# touch.net
KiCad netlist of a schematic drawn in EAGLE
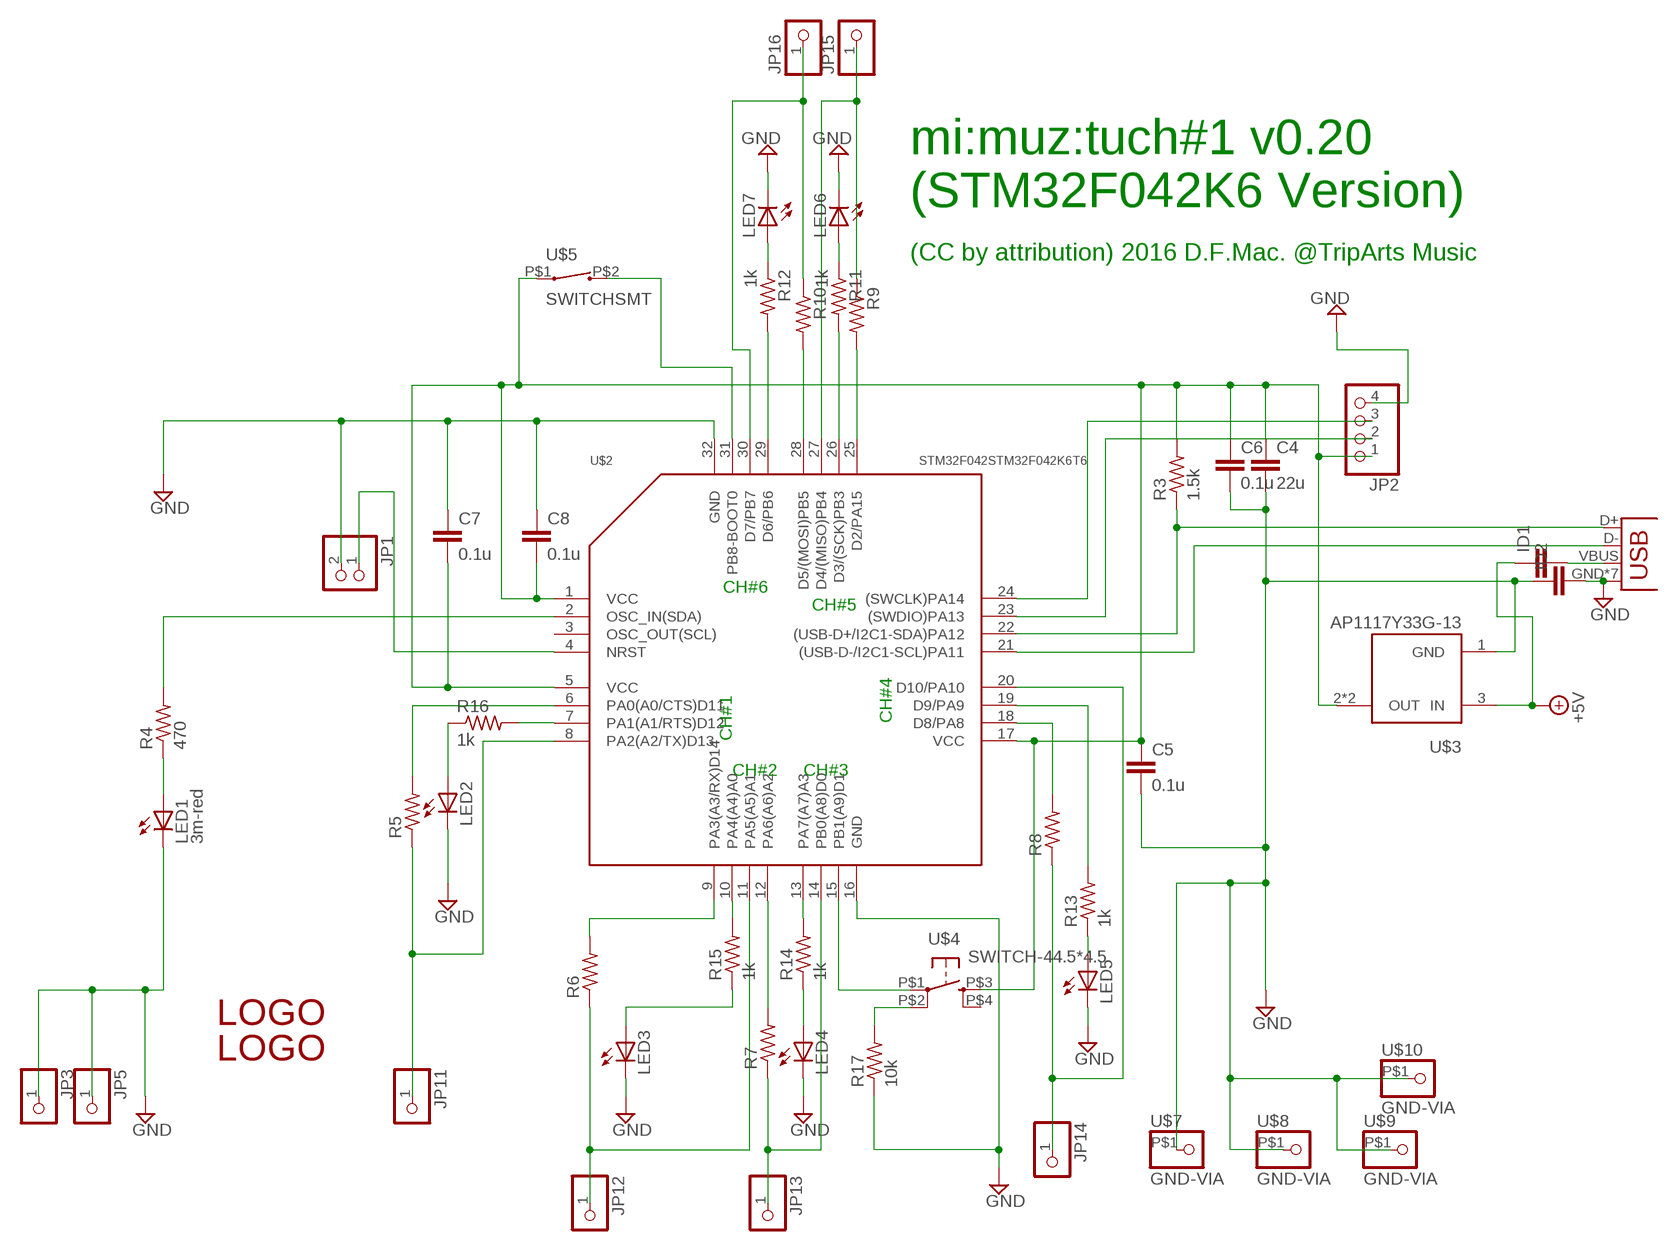
[diagram p0: schematic, sheet 1]

(export (version "E")
  (design (tool "Eeschema 10.0.6"))
  (components
    (comp (ref "C4")
      (value "22u")
      (footprint "eagle-import:C0805")
      (libsource (lib "eagle-import") (part "C-EUC0805"))
    )
    (comp (ref "C5")
      (value "0.1u")
      (footprint "eagle-import:C0603")
      (libsource (lib "eagle-import") (part "C-EUC0603"))
    )
    (comp (ref "C6")
      (value "0.1u")
      (footprint "eagle-import:C0603")
      (libsource (lib "eagle-import") (part "C-EUC0603"))
    )
    (comp (ref "C7")
      (value "0.1u")
      (footprint "eagle-import:C0603")
      (libsource (lib "eagle-import") (part "C-EUC0603"))
    )
    (comp (ref "C8")
      (value "0.1u")
      (footprint "eagle-import:C0603")
      (libsource (lib "eagle-import") (part "C-EUC0603"))
    )
    (comp (ref "ID1")
      (value "C-EUC0805")
      (footprint "eagle-import:C0805")
      (libsource (lib "eagle-import") (part "C-EUC0805"))
    )
    (comp (ref "ID2")
      (value "C-EUC0805")
      (footprint "eagle-import:C0805")
      (libsource (lib "eagle-import") (part "C-EUC0805"))
    )
    (comp (ref "JP1")
      (value "PINHD-1X2")
      (footprint "eagle-import:1X02")
      (libsource (lib "eagle-import") (part "PINHD-1X2"))
    )
    (comp (ref "JP2")
      (value "PINHD-1X4")
      (footprint "eagle-import:1X04")
      (libsource (lib "eagle-import") (part "PINHD-1X4"))
    )
    (comp (ref "JP3")
      (value "PINHD-1X13MM")
      (footprint "eagle-import:1X01")
      (libsource (lib "eagle-import") (part "PINHD-1X13MM"))
    )
    (comp (ref "JP4")
      (value "USB-MICROB")
      (footprint "eagle-import:USB-MICROB")
      (libsource (lib "eagle-import") (part "USB-MICROB"))
    )
    (comp (ref "JP5")
      (value "PINHD-1X13MM")
      (footprint "eagle-import:1X01")
      (libsource (lib "eagle-import") (part "PINHD-1X13MM"))
    )
    (comp (ref "JP11")
      (value "PINHD-1X15MM")
      (footprint "eagle-import:1X01-LARGE")
      (libsource (lib "eagle-import") (part "PINHD-1X15MM"))
    )
    (comp (ref "JP12")
      (value "PINHD-1X15MM")
      (footprint "eagle-import:1X01-LARGE")
      (libsource (lib "eagle-import") (part "PINHD-1X15MM"))
    )
    (comp (ref "JP13")
      (value "PINHD-1X15MM")
      (footprint "eagle-import:1X01-LARGE")
      (libsource (lib "eagle-import") (part "PINHD-1X15MM"))
    )
    (comp (ref "JP14")
      (value "PINHD-1X15MM")
      (footprint "eagle-import:1X01-LARGE")
      (libsource (lib "eagle-import") (part "PINHD-1X15MM"))
    )
    (comp (ref "JP15")
      (value "PINHD-1X15MM")
      (footprint "eagle-import:1X01-LARGE")
      (libsource (lib "eagle-import") (part "PINHD-1X15MM"))
    )
    (comp (ref "JP16")
      (value "PINHD-1X15MM")
      (footprint "eagle-import:1X01-LARGE")
      (libsource (lib "eagle-import") (part "PINHD-1X15MM"))
    )
    (comp (ref "LED1")
      (value "3m-red")
      (footprint "eagle-import:LED3MM")
      (libsource (lib "eagle-import") (part "LED3MM"))
    )
    (comp (ref "LED2")
      (value "LED3MM")
      (footprint "eagle-import:LED3MM")
      (libsource (lib "eagle-import") (part "LED3MM"))
    )
    (comp (ref "LED3")
      (value "LED3MM")
      (footprint "eagle-import:LED3MM")
      (libsource (lib "eagle-import") (part "LED3MM"))
    )
    (comp (ref "LED4")
      (value "LED3MM")
      (footprint "eagle-import:LED3MM")
      (libsource (lib "eagle-import") (part "LED3MM"))
    )
    (comp (ref "LED5")
      (value "LED3MM")
      (footprint "eagle-import:LED3MM")
      (libsource (lib "eagle-import") (part "LED3MM"))
    )
    (comp (ref "LED6")
      (value "LED3MM")
      (footprint "eagle-import:LED3MM")
      (libsource (lib "eagle-import") (part "LED3MM"))
    )
    (comp (ref "LED7")
      (value "LED3MM")
      (footprint "eagle-import:LED3MM")
      (libsource (lib "eagle-import") (part "LED3MM"))
    )
    (comp (ref "R3")
      (value "1.5k")
      (footprint "eagle-import:R0603")
      (libsource (lib "eagle-import") (part "R-US_R0603"))
    )
    (comp (ref "R4")
      (value "470")
      (footprint "eagle-import:R0603")
      (libsource (lib "eagle-import") (part "R-US_R0603"))
    )
    (comp (ref "R5")
      (value "R-US_R0805")
      (footprint "eagle-import:R0805")
      (libsource (lib "eagle-import") (part "R-US_R0805"))
    )
    (comp (ref "R6")
      (value "R-US_R0805")
      (footprint "eagle-import:R0805")
      (libsource (lib "eagle-import") (part "R-US_R0805"))
    )
    (comp (ref "R7")
      (value "R-US_R0805")
      (footprint "eagle-import:R0805")
      (libsource (lib "eagle-import") (part "R-US_R0805"))
    )
    (comp (ref "R8")
      (value "R-US_R0805")
      (footprint "eagle-import:R0805")
      (libsource (lib "eagle-import") (part "R-US_R0805"))
    )
    (comp (ref "R9")
      (value "R-US_R0805")
      (footprint "eagle-import:R0805")
      (libsource (lib "eagle-import") (part "R-US_R0805"))
    )
    (comp (ref "R10")
      (value "R-US_R0805")
      (footprint "eagle-import:R0805")
      (libsource (lib "eagle-import") (part "R-US_R0805"))
    )
    (comp (ref "R11")
      (value "1k")
      (footprint "eagle-import:R0603")
      (libsource (lib "eagle-import") (part "R-US_R0603"))
    )
    (comp (ref "R12")
      (value "1k")
      (footprint "eagle-import:R0603")
      (libsource (lib "eagle-import") (part "R-US_R0603"))
    )
    (comp (ref "R13")
      (value "1k")
      (footprint "eagle-import:R0603")
      (libsource (lib "eagle-import") (part "R-US_R0603"))
    )
    (comp (ref "R14")
      (value "1k")
      (footprint "eagle-import:R0603")
      (libsource (lib "eagle-import") (part "R-US_R0603"))
    )
    (comp (ref "R15")
      (value "1k")
      (footprint "eagle-import:R0603")
      (libsource (lib "eagle-import") (part "R-US_R0603"))
    )
    (comp (ref "R16")
      (value "1k")
      (footprint "eagle-import:R0603")
      (libsource (lib "eagle-import") (part "R-US_R0603"))
    )
    (comp (ref "R17")
      (value "10k")
      (footprint "eagle-import:R0603")
      (libsource (lib "eagle-import") (part "R-US_R0603"))
    )
    (comp (ref "U$1")
      (value "LOGOSMALL")
      (footprint "eagle-import:LOGO-SMALL")
      (libsource (lib "eagle-import") (part "LOGOSMALL"))
    )
    (comp (ref "U$2")
      (value "STM32F042STM32F042K6T6")
      (footprint "eagle-import:TQFP32")
      (libsource (lib "eagle-import") (part "STM32F042STM32F042K6T6"))
    )
    (comp (ref "U$3")
      (value "AP1117Y33G-13")
      (footprint "eagle-import:SOT89")
      (libsource (lib "eagle-import") (part "AP1117Y33G-13"))
    )
    (comp (ref "U$4")
      (value "SWITCH-44.5*4.5")
      (footprint "eagle-import:SWITCH-SMT-4.5_4.5")
      (libsource (lib "eagle-import") (part "SWITCH-44.54.5"))
    )
    (comp (ref "U$5")
      (value "SWITCHSMT")
      (footprint "eagle-import:SWITCH-SMT-2_4_3")
      (libsource (lib "eagle-import") (part "SWITCHSMT"))
    )
    (comp (ref "U$6")
      (value "LOGOSMALL")
      (footprint "eagle-import:LOGO-SMALL")
      (libsource (lib "eagle-import") (part "LOGOSMALL"))
    )
    (comp (ref "U$7")
      (value "GND-VIA")
      (footprint "eagle-import:GND-VIA")
      (libsource (lib "eagle-import") (part "GND-VIA"))
    )
    (comp (ref "U$8")
      (value "GND-VIA")
      (footprint "eagle-import:GND-VIA")
      (libsource (lib "eagle-import") (part "GND-VIA"))
    )
    (comp (ref "U$9")
      (value "GND-VIA")
      (footprint "eagle-import:GND-VIA")
      (libsource (lib "eagle-import") (part "GND-VIA"))
    )
    (comp (ref "U$10")
      (value "GND-VIA")
      (footprint "eagle-import:GND-VIA")
      (libsource (lib "eagle-import") (part "GND-VIA"))
    )
  )
  (nets
    (net (code "1") (name "+5V") (class "Default")
      (node (ref "ID1") (pin "1") (pinfunction "1_1") (pintype "passive"))
      (node (ref "U$3") (pin "3") (pinfunction "IN_3") (pintype "bidirectional"))
    )
    (net (code "2") (name "GND") (class "Default")
      (node (ref "C4") (pin "2") (pinfunction "2_2") (pintype "passive"))
      (node (ref "C5") (pin "2") (pinfunction "2_2") (pintype "passive"))
      (node (ref "C6") (pin "2") (pinfunction "2_2") (pintype "passive"))
      (node (ref "C7") (pin "1") (pinfunction "1_1") (pintype "passive"))
      (node (ref "C8") (pin "1") (pinfunction "1_1") (pintype "passive"))
      (node (ref "ID2") (pin "1") (pinfunction "1_1") (pintype "passive"))
      (node (ref "ID2") (pin "2") (pinfunction "2_2") (pintype "passive"))
      (node (ref "JP1") (pin "2") (pinfunction "2_2") (pintype "passive"))
      (node (ref "JP2") (pin "4") (pinfunction "4_4") (pintype "passive"))
      (node (ref "JP3") (pin "1") (pinfunction "1_1") (pintype "passive"))
      (node (ref "JP4") (pin "GND") (pinfunction "GND_GND") (pintype "bidirectional"))
      (node (ref "JP4") (pin "MT1") (pinfunction "GND_MT1") (pintype "bidirectional"))
      (node (ref "JP4") (pin "MT3") (pinfunction "GND_MT3") (pintype "bidirectional"))
      (node (ref "JP4") (pin "P$2") (pinfunction "GND_P$2") (pintype "bidirectional"))
      (node (ref "JP4") (pin "P$4") (pinfunction "GND_P$4") (pintype "bidirectional"))
      (node (ref "JP4") (pin "P$5") (pinfunction "GND_P$5") (pintype "bidirectional"))
      (node (ref "JP4") (pin "P$6") (pinfunction "GND_P$6") (pintype "bidirectional"))
      (node (ref "JP5") (pin "1") (pinfunction "1_1") (pintype "passive"))
      (node (ref "LED1") (pin "K") (pinfunction "C_K") (pintype "passive"))
      (node (ref "LED2") (pin "K") (pinfunction "C_K") (pintype "passive"))
      (node (ref "LED3") (pin "K") (pinfunction "C_K") (pintype "passive"))
      (node (ref "LED4") (pin "K") (pinfunction "C_K") (pintype "passive"))
      (node (ref "LED5") (pin "K") (pinfunction "C_K") (pintype "passive"))
      (node (ref "LED6") (pin "K") (pinfunction "C_K") (pintype "passive"))
      (node (ref "LED7") (pin "K") (pinfunction "C_K") (pintype "passive"))
      (node (ref "R17") (pin "1") (pinfunction "1_1") (pintype "passive"))
      (node (ref "U$10") (pin "P$1") (pinfunction "1_P$1") (pintype "passive"))
      (node (ref "U$2") (pin "16") (pinfunction "GND_16") (pintype "bidirectional"))
      (node (ref "U$2") (pin "32") (pinfunction "GND_32") (pintype "bidirectional"))
      (node (ref "U$3") (pin "1") (pinfunction "GND_1") (pintype "bidirectional"))
      (node (ref "U$7") (pin "P$1") (pinfunction "1_P$1") (pintype "passive"))
      (node (ref "U$8") (pin "P$1") (pinfunction "1_P$1") (pintype "passive"))
      (node (ref "U$9") (pin "P$1") (pinfunction "1_P$1") (pintype "passive"))
    )
    (net (code "3") (name "Net-(ID1-Pad2)") (class "Default")
      (node (ref "ID1") (pin "2") (pinfunction "2_2") (pintype "passive"))
      (node (ref "JP4") (pin "VBUS") (pinfunction "VBUS_VBUS") (pintype "bidirectional"))
    )
    (net (code "4") (name "Net-(LED1-PadA)") (class "Default")
      (node (ref "LED1") (pin "A") (pinfunction "A_A") (pintype "passive"))
      (node (ref "R4") (pin "1") (pinfunction "1_1") (pintype "passive"))
    )
    (net (code "5") (name "Net-(LED2-PadA)") (class "Default")
      (node (ref "LED2") (pin "A") (pinfunction "A_A") (pintype "passive"))
      (node (ref "R16") (pin "1") (pinfunction "1_1") (pintype "passive"))
    )
    (net (code "6") (name "Net-(LED3-PadA)") (class "Default")
      (node (ref "LED3") (pin "A") (pinfunction "A_A") (pintype "passive"))
      (node (ref "R15") (pin "1") (pinfunction "1_1") (pintype "passive"))
    )
    (net (code "7") (name "Net-(LED4-PadA)") (class "Default")
      (node (ref "LED4") (pin "A") (pinfunction "A_A") (pintype "passive"))
      (node (ref "R14") (pin "1") (pinfunction "1_1") (pintype "passive"))
    )
    (net (code "8") (name "Net-(LED5-PadA)") (class "Default")
      (node (ref "LED5") (pin "A") (pinfunction "A_A") (pintype "passive"))
      (node (ref "R13") (pin "1") (pinfunction "1_1") (pintype "passive"))
    )
    (net (code "9") (name "Net-(LED6-PadA)") (class "Default")
      (node (ref "LED6") (pin "A") (pinfunction "A_A") (pintype "passive"))
      (node (ref "R11") (pin "1") (pinfunction "1_1") (pintype "passive"))
    )
    (net (code "10") (name "Net-(LED7-PadA)") (class "Default")
      (node (ref "LED7") (pin "A") (pinfunction "A_A") (pintype "passive"))
      (node (ref "R12") (pin "1") (pinfunction "1_1") (pintype "passive"))
    )
    (net (code "11") (name "Net-(U$2-(SWCLK)PA14)") (class "Default")
      (node (ref "JP2") (pin "3") (pinfunction "3_3") (pintype "passive"))
      (node (ref "U$2") (pin "24") (pinfunction "(SWCLK)PA14_24") (pintype "bidirectional"))
    )
    (net (code "12") (name "Net-(U$2-(SWDIO)PA13)") (class "Default")
      (node (ref "JP2") (pin "2") (pinfunction "2_2") (pintype "passive"))
      (node (ref "U$2") (pin "23") (pinfunction "(SWDIO)PA13_23") (pintype "bidirectional"))
    )
    (net (code "13") (name "Net-(U$2-(USB-D+{slash}I2C1-SDA)PA12)") (class "Default")
      (node (ref "JP4") (pin "D+") (pinfunction "D+_D+") (pintype "bidirectional"))
      (node (ref "R3") (pin "1") (pinfunction "1_1") (pintype "passive"))
      (node (ref "U$2") (pin "22") (pinfunction "(USB-D+/I2C1-SDA)PA12_22") (pintype "bidirectional"))
    )
    (net (code "14") (name "Net-(U$2-(USB-D-{slash}I2C1-SCL)PA11)") (class "Default")
      (node (ref "JP4") (pin "D-") (pinfunction "D-_D-") (pintype "bidirectional"))
      (node (ref "U$2") (pin "21") (pinfunction "(USB-D-/I2C1-SCL)PA11_21") (pintype "bidirectional"))
    )
    (net (code "15") (name "Net-(U$2-D2{slash}PA15)") (class "Default")
      (node (ref "R9") (pin "2") (pinfunction "2_2") (pintype "passive"))
      (node (ref "U$2") (pin "25") (pinfunction "D2/PA15_25") (pintype "bidirectional"))
    )
    (net (code "16") (name "Net-(U$2-D3{slash}(SCK)PB3)") (class "Default")
      (node (ref "R11") (pin "2") (pinfunction "2_2") (pintype "passive"))
      (node (ref "U$2") (pin "26") (pinfunction "D3/(SCK)PB3_26") (pintype "bidirectional"))
    )
    (net (code "17") (name "Net-(U$2-D4{slash}(MISO)PB4)") (class "Default")
      (node (ref "JP15") (pin "1") (pinfunction "1_1") (pintype "passive"))
      (node (ref "R9") (pin "1") (pinfunction "1_1") (pintype "passive"))
      (node (ref "U$2") (pin "27") (pinfunction "D4/(MISO)PB4_27") (pintype "bidirectional"))
    )
    (net (code "18") (name "Net-(U$2-D5{slash}(MOSI)PB5)") (class "Default")
      (node (ref "R10") (pin "2") (pinfunction "2_2") (pintype "passive"))
      (node (ref "U$2") (pin "28") (pinfunction "D5/(MOSI)PB5_28") (pintype "bidirectional"))
    )
    (net (code "19") (name "Net-(U$2-D6{slash}PB6)") (class "Default")
      (node (ref "R12") (pin "2") (pinfunction "2_2") (pintype "passive"))
      (node (ref "U$2") (pin "29") (pinfunction "D6/PB6_29") (pintype "bidirectional"))
    )
    (net (code "20") (name "Net-(U$2-D7{slash}PB7)") (class "Default")
      (node (ref "JP16") (pin "1") (pinfunction "1_1") (pintype "passive"))
      (node (ref "R10") (pin "1") (pinfunction "1_1") (pintype "passive"))
      (node (ref "U$2") (pin "30") (pinfunction "D7/PB7_30") (pintype "bidirectional"))
    )
    (net (code "21") (name "Net-(U$2-D8{slash}PA8)") (class "Default")
      (node (ref "R8") (pin "2") (pinfunction "2_2") (pintype "passive"))
      (node (ref "U$2") (pin "18") (pinfunction "D8/PA8_18") (pintype "bidirectional"))
    )
    (net (code "22") (name "Net-(U$2-D9{slash}PA9)") (class "Default")
      (node (ref "R13") (pin "2") (pinfunction "2_2") (pintype "passive"))
      (node (ref "U$2") (pin "19") (pinfunction "D9/PA9_19") (pintype "bidirectional"))
    )
    (net (code "23") (name "Net-(U$2-D10{slash}PA10)") (class "Default")
      (node (ref "JP14") (pin "1") (pinfunction "1_1") (pintype "passive"))
      (node (ref "R8") (pin "1") (pinfunction "1_1") (pintype "passive"))
      (node (ref "U$2") (pin "20") (pinfunction "D10/PA10_20") (pintype "bidirectional"))
    )
    (net (code "24") (name "Net-(U$2-NRST)") (class "Default")
      (node (ref "JP1") (pin "1") (pinfunction "1_1") (pintype "passive"))
      (node (ref "U$2") (pin "4") (pinfunction "NRST_4") (pintype "bidirectional"))
    )
    (net (code "25") (name "Net-(U$2-OSC_IN(SDA))") (class "Default")
      (node (ref "R4") (pin "2") (pinfunction "2_2") (pintype "passive"))
      (node (ref "U$2") (pin "2") (pinfunction "OSC_IN(SDA)_2") (pintype "bidirectional"))
    )
    (net (code "26") (name "Net-(U$2-PA0(A0{slash}CTS)D11)") (class "Default")
      (node (ref "R5") (pin "2") (pinfunction "2_2") (pintype "passive"))
      (node (ref "U$2") (pin "6") (pinfunction "PA0(A0/CTS)D11_6") (pintype "bidirectional"))
    )
    (net (code "27") (name "Net-(U$2-PA1(A1{slash}RTS)D12)") (class "Default")
      (node (ref "R16") (pin "2") (pinfunction "2_2") (pintype "passive"))
      (node (ref "U$2") (pin "7") (pinfunction "PA1(A1/RTS)D12_7") (pintype "bidirectional"))
    )
    (net (code "28") (name "Net-(U$2-PA2(A2{slash}TX)D13)") (class "Default")
      (node (ref "JP11") (pin "1") (pinfunction "1_1") (pintype "passive"))
      (node (ref "R5") (pin "1") (pinfunction "1_1") (pintype "passive"))
      (node (ref "U$2") (pin "8") (pinfunction "PA2(A2/TX)D13_8") (pintype "bidirectional"))
    )
    (net (code "29") (name "Net-(U$2-PA3(A3{slash}RX)D14)") (class "Default")
      (node (ref "R6") (pin "2") (pinfunction "2_2") (pintype "passive"))
      (node (ref "U$2") (pin "9") (pinfunction "PA3(A3/RX)D14_9") (pintype "bidirectional"))
    )
    (net (code "30") (name "Net-(U$2-PA4(A4)A0)") (class "Default")
      (node (ref "R15") (pin "2") (pinfunction "2_2") (pintype "passive"))
      (node (ref "U$2") (pin "10") (pinfunction "PA4(A4)A0_10") (pintype "bidirectional"))
    )
    (net (code "31") (name "Net-(U$2-PA5(A5)A1)") (class "Default")
      (node (ref "JP12") (pin "1") (pinfunction "1_1") (pintype "passive"))
      (node (ref "R6") (pin "1") (pinfunction "1_1") (pintype "passive"))
      (node (ref "U$2") (pin "11") (pinfunction "PA5(A5)A1_11") (pintype "bidirectional"))
    )
    (net (code "32") (name "Net-(U$2-PA6(A6)A2)") (class "Default")
      (node (ref "R7") (pin "2") (pinfunction "2_2") (pintype "passive"))
      (node (ref "U$2") (pin "12") (pinfunction "PA6(A6)A2_12") (pintype "bidirectional"))
    )
    (net (code "33") (name "Net-(U$2-PA7(A7)A3)") (class "Default")
      (node (ref "R14") (pin "2") (pinfunction "2_2") (pintype "passive"))
      (node (ref "U$2") (pin "13") (pinfunction "PA7(A7)A3_13") (pintype "bidirectional"))
    )
    (net (code "34") (name "Net-(U$2-PB0(A8)D0)") (class "Default")
      (node (ref "JP13") (pin "1") (pinfunction "1_1") (pintype "passive"))
      (node (ref "R7") (pin "1") (pinfunction "1_1") (pintype "passive"))
      (node (ref "U$2") (pin "14") (pinfunction "PB0(A8)D0_14") (pintype "bidirectional"))
    )
    (net (code "35") (name "Net-(U$2-PB1(A9)D1)") (class "Default")
      (node (ref "U$2") (pin "15") (pinfunction "PB1(A9)D1_15") (pintype "bidirectional"))
      (node (ref "U$4") (pin "P$1") (pinfunction "P_P$1") (pintype "passive"))
    )
    (net (code "36") (name "Net-(U$2-PB8-BOOT0)") (class "Default")
      (node (ref "U$2") (pin "31") (pinfunction "PB8-BOOT0_31") (pintype "bidirectional"))
      (node (ref "U$5") (pin "P$2") (pinfunction "2_P$2") (pintype "passive"))
    )
    (net (code "37") (name "Net-(U$4-P1)") (class "Default")
      (node (ref "R17") (pin "2") (pinfunction "2_2") (pintype "passive"))
      (node (ref "U$4") (pin "P$2") (pinfunction "P1_P$2") (pintype "passive"))
    )
    (net (code "38") (name "Net-(U$4-S)") (class "Default")
      (node (ref "C4") (pin "1") (pinfunction "1_1") (pintype "passive"))
      (node (ref "C5") (pin "1") (pinfunction "1_1") (pintype "passive"))
      (node (ref "C6") (pin "1") (pinfunction "1_1") (pintype "passive"))
      (node (ref "C7") (pin "2") (pinfunction "2_2") (pintype "passive"))
      (node (ref "C8") (pin "2") (pinfunction "2_2") (pintype "passive"))
      (node (ref "JP2") (pin "1") (pinfunction "1_1") (pintype "passive"))
      (node (ref "R3") (pin "2") (pinfunction "2_2") (pintype "passive"))
      (node (ref "U$2") (pin "1") (pinfunction "VCC_1") (pintype "bidirectional"))
      (node (ref "U$2") (pin "17") (pinfunction "VCC_17") (pintype "bidirectional"))
      (node (ref "U$2") (pin "5") (pinfunction "VCC_5") (pintype "bidirectional"))
      (node (ref "U$3") (pin "2") (pinfunction "OUT_2") (pintype "bidirectional"))
      (node (ref "U$3") (pin "2@1") (pinfunction "OUT_2@1") (pintype "bidirectional"))
      (node (ref "U$4") (pin "P$3") (pinfunction "S_P$3") (pintype "passive"))
      (node (ref "U$5") (pin "P$1") (pinfunction "1_P$1") (pintype "passive"))
    )
    (net (code "39") (name "unconnected-(U$2-OSC_OUT(SCL)-Pad3)") (class "Default")
      (node (ref "U$2") (pin "3") (pinfunction "OSC_OUT(SCL)_3") (pintype "bidirectional"))
    )
    (net (code "40") (name "unconnected-(U$4-S1-PadP$4)") (class "Default")
      (node (ref "U$4") (pin "P$4") (pinfunction "S1_P$4") (pintype "passive"))
    )
  )
)
